# Project_5.net
KiCad netlist of a schematic drawn in EAGLE
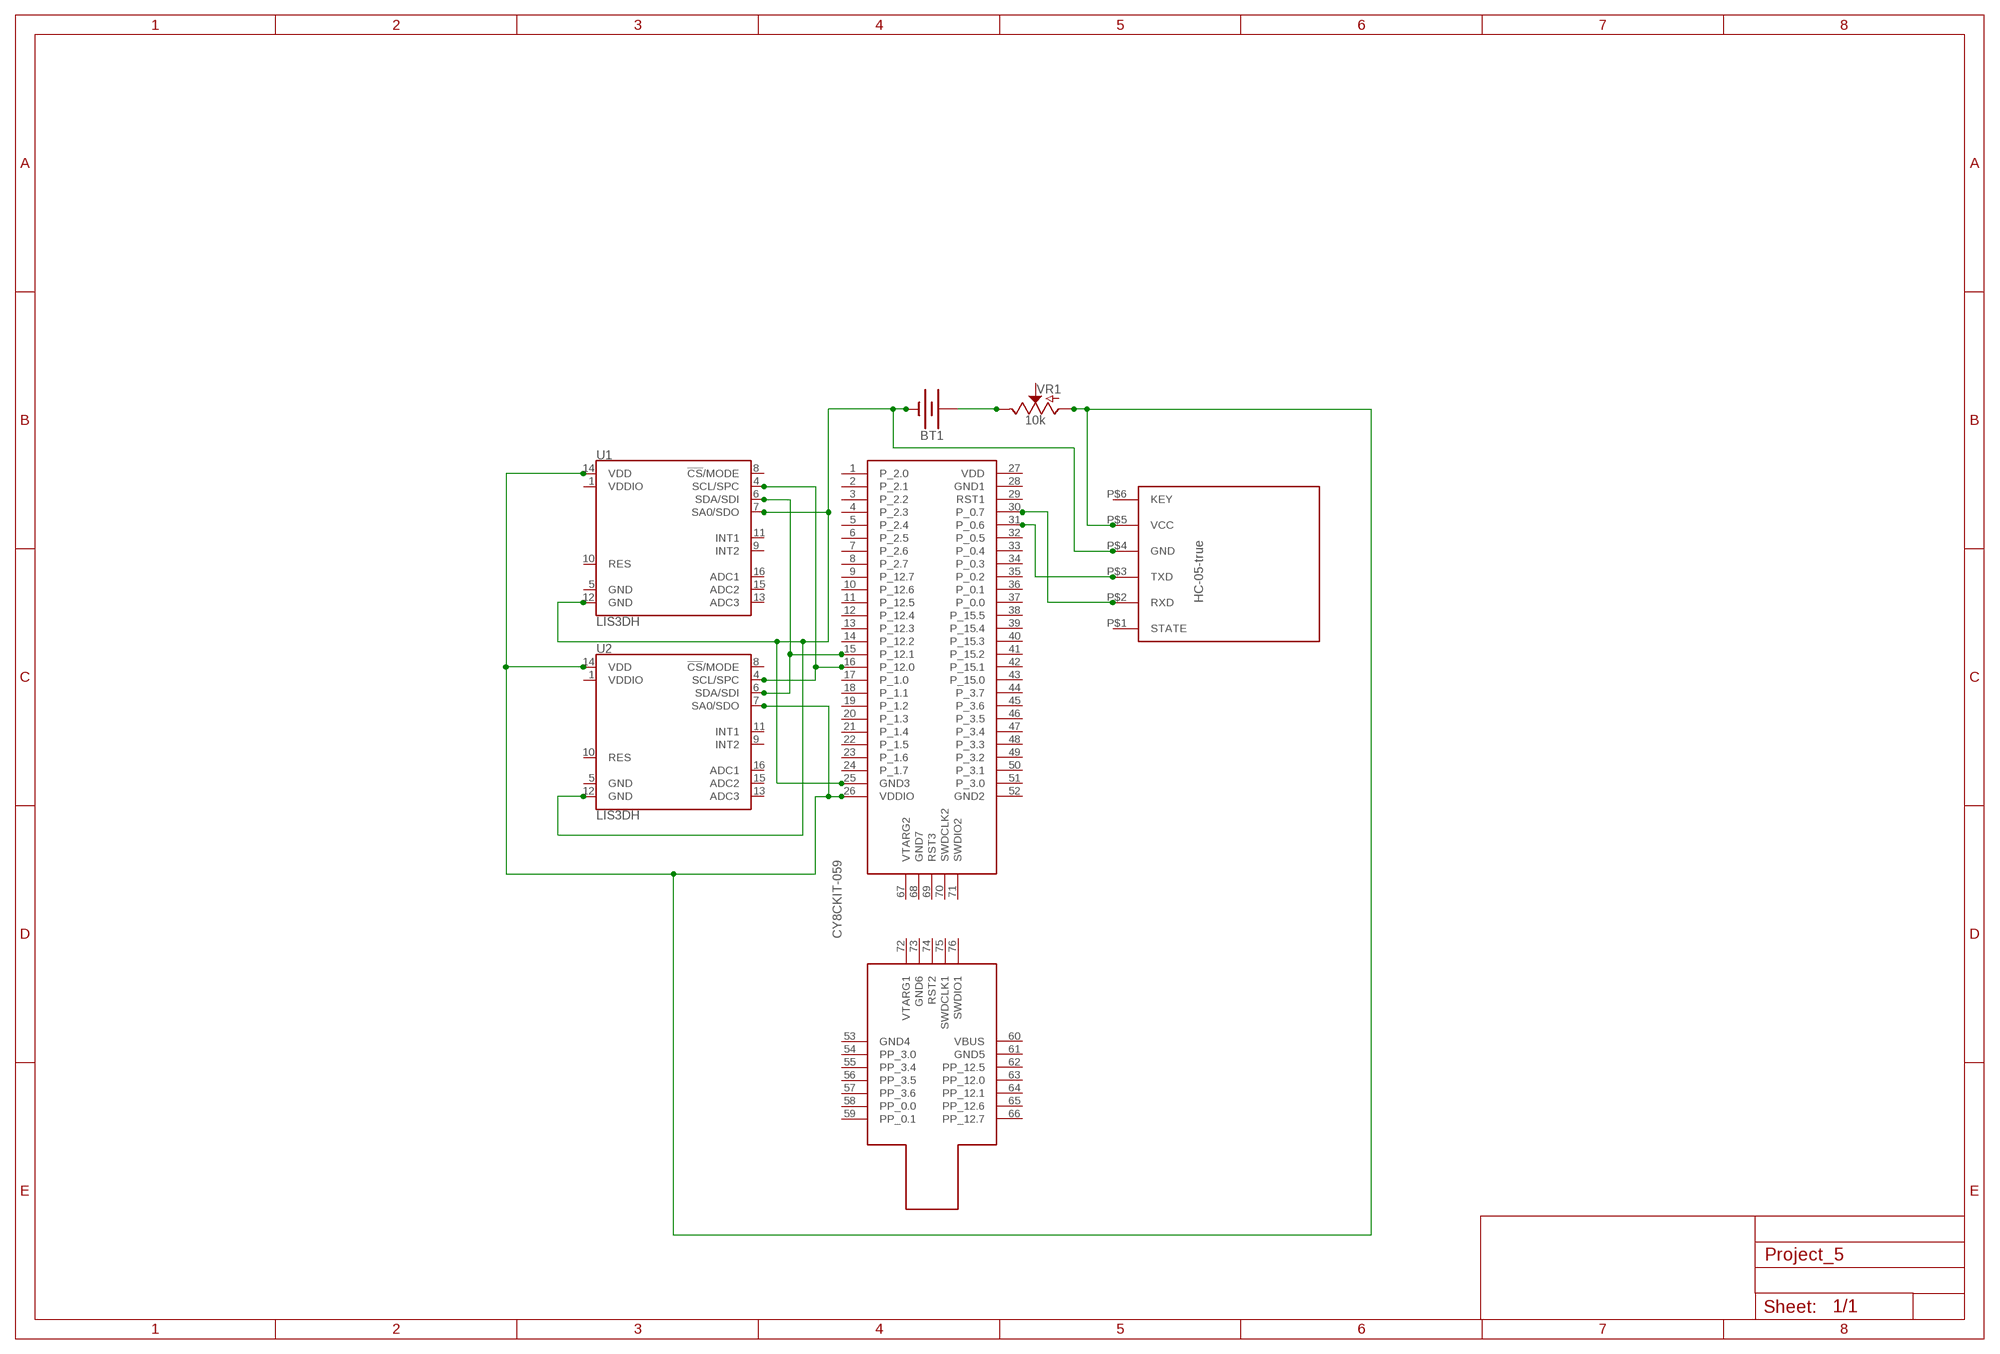
[diagram p0: schematic, sheet 1]

(export (version "E")
  (design (tool "Eeschema 10.0.6"))
  (components
    (comp (ref "BT1")
      (value "BATTERY-9V")
      (footprint "eagle-import:BATTCON_9V")
      (libsource (lib "eagle-import") (part "BATTERY-9V"))
    )
    (comp (ref "U$1")
      (value "CY8CKIT-059")
      (footprint "eagle-import:CY8CKIT-059")
      (libsource (lib "eagle-import") (part "CY8CKIT-059"))
    )
    (comp (ref "U$2")
      (value "HC")
      (footprint "eagle-import:HC-05")
      (libsource (lib "eagle-import") (part "HC"))
    )
    (comp (ref "U1")
      (value "LIS3DH")
      (footprint "eagle-import:LGA-16-3X3")
      (libsource (lib "eagle-import") (part "LIS3DH"))
    )
    (comp (ref "U2")
      (value "LIS3DH")
      (footprint "eagle-import:LGA-16-3X3")
      (libsource (lib "eagle-import") (part "LIS3DH"))
    )
    (comp (ref "VR1")
      (value "10k")
      (footprint "eagle-import:POT-PTH-ALPS-KIT")
      (libsource (lib "eagle-import") (part "POTENTIOMETER-PTH-9MM-1/20W-20%-KIT"))
    )
  )
  (nets
    (net (code "1") (name "Net-(U$1-GND3)") (class "Default")
      (node (ref "BT1") (pin "-") (pinfunction "-_-") (pintype "power_in"))
      (node (ref "U$1") (pin "25") (pinfunction "GND3_25") (pintype "bidirectional"))
      (node (ref "U$2") (pin "P$4") (pinfunction "GND_P$4") (pintype "bidirectional"))
      (node (ref "U1") (pin "12") (pinfunction "GND_12") (pintype "bidirectional"))
      (node (ref "U1") (pin "7") (pinfunction "SA0/SDO_7") (pintype "bidirectional"))
      (node (ref "U2") (pin "12") (pinfunction "GND_12") (pintype "bidirectional"))
    )
    (net (code "2") (name "Net-(U$1-P_0.6)") (class "Default")
      (node (ref "U$1") (pin "31") (pinfunction "P_0.6_31") (pintype "bidirectional"))
      (node (ref "U$2") (pin "P$3") (pinfunction "TXD_P$3") (pintype "bidirectional"))
    )
    (net (code "3") (name "Net-(U$1-P_0.7)") (class "Default")
      (node (ref "U$1") (pin "30") (pinfunction "P_0.7_30") (pintype "bidirectional"))
      (node (ref "U$2") (pin "P$2") (pinfunction "RXD_P$2") (pintype "bidirectional"))
    )
    (net (code "4") (name "Net-(U$1-P_12.0)") (class "Default")
      (node (ref "U$1") (pin "16") (pinfunction "P_12.0_16") (pintype "bidirectional"))
      (node (ref "U1") (pin "4") (pinfunction "SCL/SPC_4") (pintype "bidirectional"))
      (node (ref "U2") (pin "4") (pinfunction "SCL/SPC_4") (pintype "bidirectional"))
    )
    (net (code "5") (name "Net-(U$1-P_12.1)") (class "Default")
      (node (ref "U$1") (pin "15") (pinfunction "P_12.1_15") (pintype "bidirectional"))
      (node (ref "U1") (pin "6") (pinfunction "SDA/SDI_6") (pintype "bidirectional"))
      (node (ref "U2") (pin "6") (pinfunction "SDA/SDI_6") (pintype "bidirectional"))
    )
    (net (code "6") (name "Net-(U$1-VDDIO)") (class "Default")
      (node (ref "U$1") (pin "26") (pinfunction "VDDIO_26") (pintype "bidirectional"))
      (node (ref "U$2") (pin "P$5") (pinfunction "VCC_P$5") (pintype "bidirectional"))
      (node (ref "U1") (pin "14") (pinfunction "VDD_14") (pintype "bidirectional"))
      (node (ref "U2") (pin "14") (pinfunction "VDD_14") (pintype "bidirectional"))
      (node (ref "U2") (pin "7") (pinfunction "SA0/SDO_7") (pintype "bidirectional"))
      (node (ref "VR1") (pin "P$3") (pinfunction "A_P$3") (pintype "passive"))
    )
    (net (code "7") (name "Net-(VR1-E)") (class "Default")
      (node (ref "BT1") (pin "+") (pinfunction "+_+") (pintype "power_in"))
      (node (ref "VR1") (pin "P$1") (pinfunction "E_P$1") (pintype "passive"))
    )
    (net (code "8") (name "unconnected-(U$1-GND1-Pad28)") (class "Default")
      (node (ref "U$1") (pin "28") (pinfunction "GND1_28") (pintype "bidirectional"))
    )
    (net (code "9") (name "unconnected-(U$1-GND2-Pad52)") (class "Default")
      (node (ref "U$1") (pin "52") (pinfunction "GND2_52") (pintype "bidirectional"))
    )
    (net (code "10") (name "unconnected-(U$1-GND4-Pad53)") (class "Default")
      (node (ref "U$1") (pin "53") (pinfunction "GND4_53") (pintype "bidirectional"))
    )
    (net (code "11") (name "unconnected-(U$1-GND5-Pad61)") (class "Default")
      (node (ref "U$1") (pin "61") (pinfunction "GND5_61") (pintype "bidirectional"))
    )
    (net (code "12") (name "unconnected-(U$1-GND6-Pad73)") (class "Default")
      (node (ref "U$1") (pin "73") (pinfunction "GND6_73") (pintype "bidirectional"))
    )
    (net (code "13") (name "unconnected-(U$1-GND7-Pad68)") (class "Default")
      (node (ref "U$1") (pin "68") (pinfunction "GND7_68") (pintype "bidirectional"))
    )
    (net (code "14") (name "unconnected-(U$1-PP_0.0-Pad58)") (class "Default")
      (node (ref "U$1") (pin "58") (pinfunction "PP_0.0_58") (pintype "bidirectional"))
    )
    (net (code "15") (name "unconnected-(U$1-PP_0.1-Pad59)") (class "Default")
      (node (ref "U$1") (pin "59") (pinfunction "PP_0.1_59") (pintype "bidirectional"))
    )
    (net (code "16") (name "unconnected-(U$1-PP_3.0-Pad54)") (class "Default")
      (node (ref "U$1") (pin "54") (pinfunction "PP_3.0_54") (pintype "bidirectional"))
    )
    (net (code "17") (name "unconnected-(U$1-PP_3.4-Pad55)") (class "Default")
      (node (ref "U$1") (pin "55") (pinfunction "PP_3.4_55") (pintype "bidirectional"))
    )
    (net (code "18") (name "unconnected-(U$1-PP_3.5-Pad56)") (class "Default")
      (node (ref "U$1") (pin "56") (pinfunction "PP_3.5_56") (pintype "bidirectional"))
    )
    (net (code "19") (name "unconnected-(U$1-PP_3.6-Pad57)") (class "Default")
      (node (ref "U$1") (pin "57") (pinfunction "PP_3.6_57") (pintype "bidirectional"))
    )
    (net (code "20") (name "unconnected-(U$1-PP_12.0-Pad63)") (class "Default")
      (node (ref "U$1") (pin "63") (pinfunction "PP_12.0_63") (pintype "bidirectional"))
    )
    (net (code "21") (name "unconnected-(U$1-PP_12.1-Pad64)") (class "Default")
      (node (ref "U$1") (pin "64") (pinfunction "PP_12.1_64") (pintype "bidirectional"))
    )
    (net (code "22") (name "unconnected-(U$1-PP_12.5-Pad62)") (class "Default")
      (node (ref "U$1") (pin "62") (pinfunction "PP_12.5_62") (pintype "bidirectional"))
    )
    (net (code "23") (name "unconnected-(U$1-PP_12.6-Pad65)") (class "Default")
      (node (ref "U$1") (pin "65") (pinfunction "PP_12.6_65") (pintype "bidirectional"))
    )
    (net (code "24") (name "unconnected-(U$1-PP_12.7-Pad66)") (class "Default")
      (node (ref "U$1") (pin "66") (pinfunction "PP_12.7_66") (pintype "bidirectional"))
    )
    (net (code "25") (name "unconnected-(U$1-P_0.0-Pad37)") (class "Default")
      (node (ref "U$1") (pin "37") (pinfunction "P_0.0_37") (pintype "bidirectional"))
    )
    (net (code "26") (name "unconnected-(U$1-P_0.1-Pad36)") (class "Default")
      (node (ref "U$1") (pin "36") (pinfunction "P_0.1_36") (pintype "bidirectional"))
    )
    (net (code "27") (name "unconnected-(U$1-P_0.2-Pad35)") (class "Default")
      (node (ref "U$1") (pin "35") (pinfunction "P_0.2_35") (pintype "bidirectional"))
    )
    (net (code "28") (name "unconnected-(U$1-P_0.3-Pad34)") (class "Default")
      (node (ref "U$1") (pin "34") (pinfunction "P_0.3_34") (pintype "bidirectional"))
    )
    (net (code "29") (name "unconnected-(U$1-P_0.4-Pad33)") (class "Default")
      (node (ref "U$1") (pin "33") (pinfunction "P_0.4_33") (pintype "bidirectional"))
    )
    (net (code "30") (name "unconnected-(U$1-P_0.5-Pad32)") (class "Default")
      (node (ref "U$1") (pin "32") (pinfunction "P_0.5_32") (pintype "bidirectional"))
    )
    (net (code "31") (name "unconnected-(U$1-P_1.0-Pad17)") (class "Default")
      (node (ref "U$1") (pin "17") (pinfunction "P_1.0_17") (pintype "bidirectional"))
    )
    (net (code "32") (name "unconnected-(U$1-P_1.1-Pad18)") (class "Default")
      (node (ref "U$1") (pin "18") (pinfunction "P_1.1_18") (pintype "bidirectional"))
    )
    (net (code "33") (name "unconnected-(U$1-P_1.2-Pad19)") (class "Default")
      (node (ref "U$1") (pin "19") (pinfunction "P_1.2_19") (pintype "bidirectional"))
    )
    (net (code "34") (name "unconnected-(U$1-P_1.3-Pad20)") (class "Default")
      (node (ref "U$1") (pin "20") (pinfunction "P_1.3_20") (pintype "bidirectional"))
    )
    (net (code "35") (name "unconnected-(U$1-P_1.4-Pad21)") (class "Default")
      (node (ref "U$1") (pin "21") (pinfunction "P_1.4_21") (pintype "bidirectional"))
    )
    (net (code "36") (name "unconnected-(U$1-P_1.5-Pad22)") (class "Default")
      (node (ref "U$1") (pin "22") (pinfunction "P_1.5_22") (pintype "bidirectional"))
    )
    (net (code "37") (name "unconnected-(U$1-P_1.6-Pad23)") (class "Default")
      (node (ref "U$1") (pin "23") (pinfunction "P_1.6_23") (pintype "bidirectional"))
    )
    (net (code "38") (name "unconnected-(U$1-P_1.7-Pad24)") (class "Default")
      (node (ref "U$1") (pin "24") (pinfunction "P_1.7_24") (pintype "bidirectional"))
    )
    (net (code "39") (name "unconnected-(U$1-P_2.0-Pad1)") (class "Default")
      (node (ref "U$1") (pin "1") (pinfunction "P_2.0_1") (pintype "bidirectional"))
    )
    (net (code "40") (name "unconnected-(U$1-P_2.1-Pad2)") (class "Default")
      (node (ref "U$1") (pin "2") (pinfunction "P_2.1_2") (pintype "bidirectional"))
    )
    (net (code "41") (name "unconnected-(U$1-P_2.2-Pad3)") (class "Default")
      (node (ref "U$1") (pin "3") (pinfunction "P_2.2_3") (pintype "bidirectional"))
    )
    (net (code "42") (name "unconnected-(U$1-P_2.3-Pad4)") (class "Default")
      (node (ref "U$1") (pin "4") (pinfunction "P_2.3_4") (pintype "bidirectional"))
    )
    (net (code "43") (name "unconnected-(U$1-P_2.4-Pad5)") (class "Default")
      (node (ref "U$1") (pin "5") (pinfunction "P_2.4_5") (pintype "bidirectional"))
    )
    (net (code "44") (name "unconnected-(U$1-P_2.5-Pad6)") (class "Default")
      (node (ref "U$1") (pin "6") (pinfunction "P_2.5_6") (pintype "bidirectional"))
    )
    (net (code "45") (name "unconnected-(U$1-P_2.6-Pad7)") (class "Default")
      (node (ref "U$1") (pin "7") (pinfunction "P_2.6_7") (pintype "bidirectional"))
    )
    (net (code "46") (name "unconnected-(U$1-P_2.7-Pad8)") (class "Default")
      (node (ref "U$1") (pin "8") (pinfunction "P_2.7_8") (pintype "bidirectional"))
    )
    (net (code "47") (name "unconnected-(U$1-P_3.0-Pad51)") (class "Default")
      (node (ref "U$1") (pin "51") (pinfunction "P_3.0_51") (pintype "bidirectional"))
    )
    (net (code "48") (name "unconnected-(U$1-P_3.1-Pad50)") (class "Default")
      (node (ref "U$1") (pin "50") (pinfunction "P_3.1_50") (pintype "bidirectional"))
    )
    (net (code "49") (name "unconnected-(U$1-P_3.2-Pad49)") (class "Default")
      (node (ref "U$1") (pin "49") (pinfunction "P_3.2_49") (pintype "bidirectional"))
    )
    (net (code "50") (name "unconnected-(U$1-P_3.3-Pad48)") (class "Default")
      (node (ref "U$1") (pin "48") (pinfunction "P_3.3_48") (pintype "bidirectional"))
    )
    (net (code "51") (name "unconnected-(U$1-P_3.4-Pad47)") (class "Default")
      (node (ref "U$1") (pin "47") (pinfunction "P_3.4_47") (pintype "bidirectional"))
    )
    (net (code "52") (name "unconnected-(U$1-P_3.5-Pad46)") (class "Default")
      (node (ref "U$1") (pin "46") (pinfunction "P_3.5_46") (pintype "bidirectional"))
    )
    (net (code "53") (name "unconnected-(U$1-P_3.6-Pad45)") (class "Default")
      (node (ref "U$1") (pin "45") (pinfunction "P_3.6_45") (pintype "bidirectional"))
    )
    (net (code "54") (name "unconnected-(U$1-P_3.7-Pad44)") (class "Default")
      (node (ref "U$1") (pin "44") (pinfunction "P_3.7_44") (pintype "bidirectional"))
    )
    (net (code "55") (name "unconnected-(U$1-P_12.2-Pad14)") (class "Default")
      (node (ref "U$1") (pin "14") (pinfunction "P_12.2_14") (pintype "bidirectional"))
    )
    (net (code "56") (name "unconnected-(U$1-P_12.3-Pad13)") (class "Default")
      (node (ref "U$1") (pin "13") (pinfunction "P_12.3_13") (pintype "bidirectional"))
    )
    (net (code "57") (name "unconnected-(U$1-P_12.4-Pad12)") (class "Default")
      (node (ref "U$1") (pin "12") (pinfunction "P_12.4_12") (pintype "bidirectional"))
    )
    (net (code "58") (name "unconnected-(U$1-P_12.5-Pad11)") (class "Default")
      (node (ref "U$1") (pin "11") (pinfunction "P_12.5_11") (pintype "bidirectional"))
    )
    (net (code "59") (name "unconnected-(U$1-P_12.6-Pad10)") (class "Default")
      (node (ref "U$1") (pin "10") (pinfunction "P_12.6_10") (pintype "bidirectional"))
    )
    (net (code "60") (name "unconnected-(U$1-P_12.7-Pad9)") (class "Default")
      (node (ref "U$1") (pin "9") (pinfunction "P_12.7_9") (pintype "bidirectional"))
    )
    (net (code "61") (name "unconnected-(U$1-P_15.0-Pad43)") (class "Default")
      (node (ref "U$1") (pin "43") (pinfunction "P_15.0_43") (pintype "bidirectional"))
    )
    (net (code "62") (name "unconnected-(U$1-P_15.1-Pad42)") (class "Default")
      (node (ref "U$1") (pin "42") (pinfunction "P_15.1_42") (pintype "bidirectional"))
    )
    (net (code "63") (name "unconnected-(U$1-P_15.2-Pad41)") (class "Default")
      (node (ref "U$1") (pin "41") (pinfunction "P_15.2_41") (pintype "bidirectional"))
    )
    (net (code "64") (name "unconnected-(U$1-P_15.3-Pad40)") (class "Default")
      (node (ref "U$1") (pin "40") (pinfunction "P_15.3_40") (pintype "bidirectional"))
    )
    (net (code "65") (name "unconnected-(U$1-P_15.4-Pad39)") (class "Default")
      (node (ref "U$1") (pin "39") (pinfunction "P_15.4_39") (pintype "bidirectional"))
    )
    (net (code "66") (name "unconnected-(U$1-P_15.5-Pad38)") (class "Default")
      (node (ref "U$1") (pin "38") (pinfunction "P_15.5_38") (pintype "bidirectional"))
    )
    (net (code "67") (name "unconnected-(U$1-RST1-Pad29)") (class "Default")
      (node (ref "U$1") (pin "29") (pinfunction "RST1_29") (pintype "bidirectional"))
    )
    (net (code "68") (name "unconnected-(U$1-RST2-Pad74)") (class "Default")
      (node (ref "U$1") (pin "74") (pinfunction "RST2_74") (pintype "bidirectional"))
    )
    (net (code "69") (name "unconnected-(U$1-RST3-Pad69)") (class "Default")
      (node (ref "U$1") (pin "69") (pinfunction "RST3_69") (pintype "bidirectional"))
    )
    (net (code "70") (name "unconnected-(U$1-SWDCLK1-Pad75)") (class "Default")
      (node (ref "U$1") (pin "75") (pinfunction "SWDCLK1_75") (pintype "bidirectional"))
    )
    (net (code "71") (name "unconnected-(U$1-SWDCLK2-Pad70)") (class "Default")
      (node (ref "U$1") (pin "70") (pinfunction "SWDCLK2_70") (pintype "bidirectional"))
    )
    (net (code "72") (name "unconnected-(U$1-SWDIO1-Pad76)") (class "Default")
      (node (ref "U$1") (pin "76") (pinfunction "SWDIO1_76") (pintype "bidirectional"))
    )
    (net (code "73") (name "unconnected-(U$1-SWDIO2-Pad71)") (class "Default")
      (node (ref "U$1") (pin "71") (pinfunction "SWDIO2_71") (pintype "bidirectional"))
    )
    (net (code "74") (name "unconnected-(U$1-VBUS-Pad60)") (class "Default")
      (node (ref "U$1") (pin "60") (pinfunction "VBUS_60") (pintype "bidirectional"))
    )
    (net (code "75") (name "unconnected-(U$1-VDD-Pad27)") (class "Default")
      (node (ref "U$1") (pin "27") (pinfunction "VDD_27") (pintype "bidirectional"))
    )
    (net (code "76") (name "unconnected-(U$1-VTARG1-Pad72)") (class "Default")
      (node (ref "U$1") (pin "72") (pinfunction "VTARG1_72") (pintype "bidirectional"))
    )
    (net (code "77") (name "unconnected-(U$1-VTARG2-Pad67)") (class "Default")
      (node (ref "U$1") (pin "67") (pinfunction "VTARG2_67") (pintype "bidirectional"))
    )
    (net (code "78") (name "unconnected-(U$2-KEY-PadP$6)") (class "Default")
      (node (ref "U$2") (pin "P$6") (pinfunction "KEY_P$6") (pintype "bidirectional"))
    )
    (net (code "79") (name "unconnected-(U$2-STATE-PadP$1)") (class "Default")
      (node (ref "U$2") (pin "P$1") (pinfunction "STATE_P$1") (pintype "bidirectional"))
    )
    (net (code "80") (name "unconnected-(U1-ADC1-Pad16)") (class "Default")
      (node (ref "U1") (pin "16") (pinfunction "ADC1_16") (pintype "bidirectional"))
    )
    (net (code "81") (name "unconnected-(U1-ADC2-Pad15)") (class "Default")
      (node (ref "U1") (pin "15") (pinfunction "ADC2_15") (pintype "bidirectional"))
    )
    (net (code "82") (name "unconnected-(U1-ADC3-Pad13)") (class "Default")
      (node (ref "U1") (pin "13") (pinfunction "ADC3_13") (pintype "bidirectional"))
    )
    (net (code "83") (name "unconnected-(U1-GND-Pad5)") (class "Default")
      (node (ref "U1") (pin "5") (pinfunction "GND_5") (pintype "bidirectional"))
    )
    (net (code "84") (name "unconnected-(U1-INT1-Pad11)") (class "Default")
      (node (ref "U1") (pin "11") (pinfunction "INT1_11") (pintype "bidirectional"))
    )
    (net (code "85") (name "unconnected-(U1-INT2-Pad9)") (class "Default")
      (node (ref "U1") (pin "9") (pinfunction "INT2_9") (pintype "bidirectional"))
    )
    (net (code "86") (name "unconnected-(U1-RES-Pad10)") (class "Default")
      (node (ref "U1") (pin "10") (pinfunction "RES_10") (pintype "bidirectional"))
    )
    (net (code "87") (name "unconnected-(U1-VDDIO-Pad1)") (class "Default")
      (node (ref "U1") (pin "1") (pinfunction "VDDIO_1") (pintype "bidirectional"))
    )
    (net (code "88") (name "unconnected-(U1-~{CS}{slash}MODE-Pad8)") (class "Default")
      (node (ref "U1") (pin "8") (pinfunction "~{CS}/MODE_8") (pintype "bidirectional"))
    )
    (net (code "89") (name "unconnected-(U2-ADC1-Pad16)") (class "Default")
      (node (ref "U2") (pin "16") (pinfunction "ADC1_16") (pintype "bidirectional"))
    )
    (net (code "90") (name "unconnected-(U2-ADC2-Pad15)") (class "Default")
      (node (ref "U2") (pin "15") (pinfunction "ADC2_15") (pintype "bidirectional"))
    )
    (net (code "91") (name "unconnected-(U2-ADC3-Pad13)") (class "Default")
      (node (ref "U2") (pin "13") (pinfunction "ADC3_13") (pintype "bidirectional"))
    )
    (net (code "92") (name "unconnected-(U2-GND-Pad5)") (class "Default")
      (node (ref "U2") (pin "5") (pinfunction "GND_5") (pintype "bidirectional"))
    )
    (net (code "93") (name "unconnected-(U2-INT1-Pad11)") (class "Default")
      (node (ref "U2") (pin "11") (pinfunction "INT1_11") (pintype "bidirectional"))
    )
    (net (code "94") (name "unconnected-(U2-INT2-Pad9)") (class "Default")
      (node (ref "U2") (pin "9") (pinfunction "INT2_9") (pintype "bidirectional"))
    )
    (net (code "95") (name "unconnected-(U2-RES-Pad10)") (class "Default")
      (node (ref "U2") (pin "10") (pinfunction "RES_10") (pintype "bidirectional"))
    )
    (net (code "96") (name "unconnected-(U2-VDDIO-Pad1)") (class "Default")
      (node (ref "U2") (pin "1") (pinfunction "VDDIO_1") (pintype "bidirectional"))
    )
    (net (code "97") (name "unconnected-(U2-~{CS}{slash}MODE-Pad8)") (class "Default")
      (node (ref "U2") (pin "8") (pinfunction "~{CS}/MODE_8") (pintype "bidirectional"))
    )
    (net (code "98") (name "unconnected-(VR1-S-PadP$2)") (class "Default")
      (node (ref "VR1") (pin "P$2") (pinfunction "S_P$2") (pintype "passive"))
    )
  )
)
